# main.net
KiCad netlist of a schematic drawn in Altium Designer
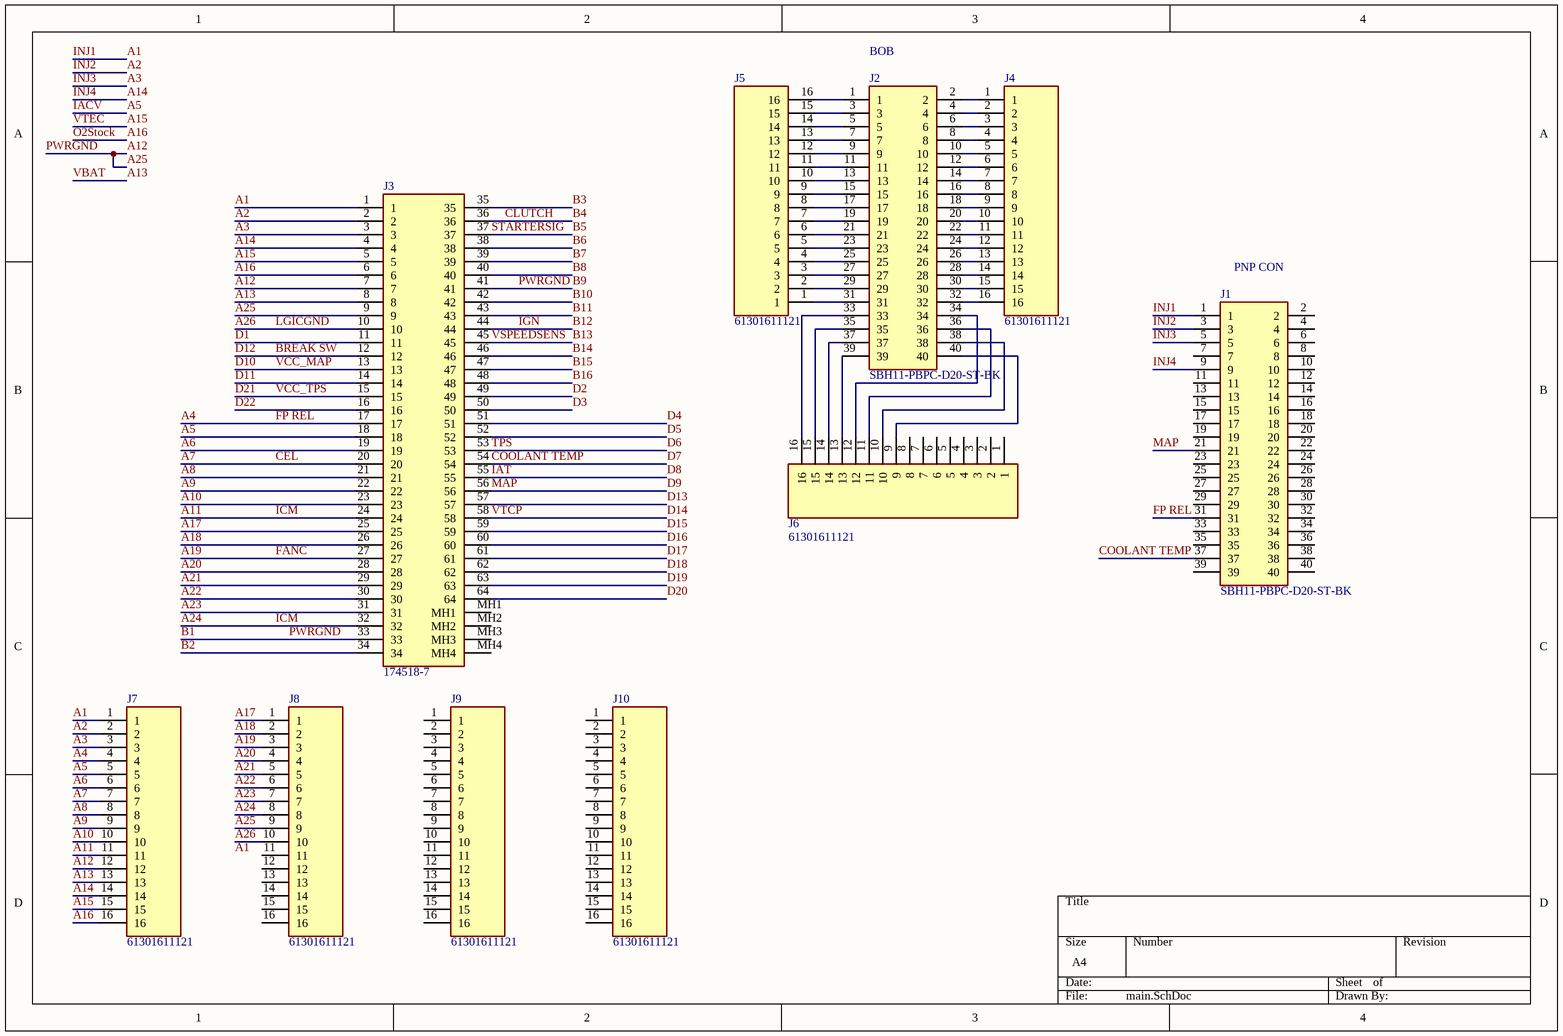
[diagram p0: main.SchDoc]

(export (version "E")
  (design (tool "Eeschema 10.0.6"))
  (components
    (comp (ref "J1")
      (value "SBH11-PBPC-D20-ST-BK")
      (footprint "SamacSys:SHDR40W64P254_2X20_5830X910X910P")
      (description "Connector")
      (libsource (lib "*") (part "SBH11-PBPC-D20-ST-BK"))
    )
    (comp (ref "J2")
      (value "SBH11-PBPC-D20-ST-BK")
      (footprint "SamacSys:SHDR40W64P254_2X20_5830X910X910P")
      (description "Connector")
      (libsource (lib "*") (part "SBH11-PBPC-D20-ST-BK"))
    )
    (comp (ref "J3")
      (value "174518-7")
      (footprint "SamacSys:1745187")
      (description "Connector")
      (fields (field (name "MOUSER PART NUMBER") "571-174518-7"))
      (libsource (lib "*") (part "174518-7"))
    )
    (comp (ref "J4")
      (value "61301611121")
      (footprint "SamacSys:HDRV16W79P0X254_1X16_4064X254X874P")
      (description "Connector")
      (fields (field (name "MOUSER PART NUMBER") "710-61301611121"))
      (libsource (lib "*") (part "61301611121"))
    )
    (comp (ref "J5")
      (value "61301611121")
      (footprint "SamacSys:HDRV16W79P0X254_1X16_4064X254X874P")
      (description "Connector")
      (fields (field (name "MOUSER PART NUMBER") "710-61301611121"))
      (libsource (lib "") (part "61301611121_2"))
    )
    (comp (ref "J6")
      (value "61301611121")
      (footprint "SamacSys:HDRV16W79P0X254_1X16_4064X254X874P")
      (description "Connector")
      (fields (field (name "MOUSER PART NUMBER") "710-61301611121"))
      (libsource (lib "") (part "61301611121_1"))
    )
    (comp (ref "J7")
      (value "61301611121")
      (footprint "SamacSys:HDRV16W79P0X254_1X16_4064X254X874P")
      (description "Connector")
      (fields (field (name "MOUSER PART NUMBER") "710-61301611121"))
      (libsource (lib "*") (part "61301611121"))
    )
    (comp (ref "J8")
      (value "61301611121")
      (footprint "SamacSys:HDRV16W79P0X254_1X16_4064X254X874P")
      (description "Connector")
      (fields (field (name "MOUSER PART NUMBER") "710-61301611121"))
      (libsource (lib "*") (part "61301611121"))
    )
    (comp (ref "J9")
      (value "61301611121")
      (footprint "SamacSys:HDRV16W79P0X254_1X16_4064X254X874P")
      (description "Connector")
      (fields (field (name "MOUSER PART NUMBER") "710-61301611121"))
      (libsource (lib "*") (part "61301611121"))
    )
    (comp (ref "J10")
      (value "61301611121")
      (footprint "SamacSys:HDRV16W79P0X254_1X16_4064X254X874P")
      (description "Connector")
      (fields (field (name "MOUSER PART NUMBER") "710-61301611121"))
      (libsource (lib "*") (part "61301611121"))
    )
  )
  (nets
    (net (code "1") (name "/A1") (class "Default")
      (node (ref "J1") (pin "1") (pinfunction "1_1") (pintype "passive"))
      (node (ref "J3") (pin "1") (pinfunction "1_1") (pintype "passive"))
      (node (ref "J7") (pin "1") (pinfunction "1_1") (pintype "passive"))
    )
    (net (code "2") (name "/A2") (class "Default")
      (node (ref "J1") (pin "3") (pinfunction "3_3") (pintype "passive"))
      (node (ref "J3") (pin "2") (pinfunction "2_2") (pintype "passive"))
      (node (ref "J7") (pin "2") (pinfunction "2_2") (pintype "passive"))
    )
    (net (code "3") (name "/A3") (class "Default")
      (node (ref "J1") (pin "5") (pinfunction "5_5") (pintype "passive"))
      (node (ref "J3") (pin "3") (pinfunction "3_3") (pintype "passive"))
      (node (ref "J7") (pin "3") (pinfunction "3_3") (pintype "passive"))
    )
    (net (code "4") (name "/A4") (class "Default")
      (node (ref "J1") (pin "31") (pinfunction "31_31") (pintype "passive"))
      (node (ref "J3") (pin "17") (pinfunction "17_17") (pintype "passive"))
      (node (ref "J7") (pin "4") (pinfunction "4_4") (pintype "passive"))
    )
    (net (code "5") (name "/A5") (class "Default")
      (node (ref "J3") (pin "18") (pinfunction "18_18") (pintype "passive"))
      (node (ref "J7") (pin "5") (pinfunction "5_5") (pintype "passive"))
    )
    (net (code "6") (name "/A6") (class "Default")
      (node (ref "J3") (pin "19") (pinfunction "19_19") (pintype "passive"))
      (node (ref "J7") (pin "6") (pinfunction "6_6") (pintype "passive"))
    )
    (net (code "7") (name "/A7") (class "Default")
      (node (ref "J3") (pin "20") (pinfunction "20_20") (pintype "passive"))
      (node (ref "J7") (pin "7") (pinfunction "7_7") (pintype "passive"))
    )
    (net (code "8") (name "/A8") (class "Default")
      (node (ref "J3") (pin "21") (pinfunction "21_21") (pintype "passive"))
      (node (ref "J7") (pin "8") (pinfunction "8_8") (pintype "passive"))
    )
    (net (code "9") (name "/A9") (class "Default")
      (node (ref "J3") (pin "22") (pinfunction "22_22") (pintype "passive"))
      (node (ref "J7") (pin "9") (pinfunction "9_9") (pintype "passive"))
    )
    (net (code "10") (name "/A10") (class "Default")
      (node (ref "J3") (pin "23") (pinfunction "23_23") (pintype "passive"))
      (node (ref "J7") (pin "10") (pinfunction "10_10") (pintype "passive"))
    )
    (net (code "11") (name "/A11") (class "Default")
      (node (ref "J3") (pin "24") (pinfunction "24_24") (pintype "passive"))
      (node (ref "J3") (pin "32") (pinfunction "32_32") (pintype "passive"))
      (node (ref "J7") (pin "11") (pinfunction "11_11") (pintype "passive"))
      (node (ref "J8") (pin "8") (pinfunction "8_8") (pintype "passive"))
    )
    (net (code "12") (name "/A12") (class "Default")
      (node (ref "J3") (pin "33") (pinfunction "33_33") (pintype "passive"))
      (node (ref "J3") (pin "41") (pinfunction "41_41") (pintype "passive"))
      (node (ref "J3") (pin "7") (pinfunction "7_7") (pintype "passive"))
      (node (ref "J3") (pin "9") (pinfunction "9_9") (pintype "passive"))
      (node (ref "J7") (pin "12") (pinfunction "12_12") (pintype "passive"))
      (node (ref "J8") (pin "9") (pinfunction "9_9") (pintype "passive"))
    )
    (net (code "13") (name "/A13") (class "Default")
      (node (ref "J3") (pin "8") (pinfunction "8_8") (pintype "passive"))
      (node (ref "J7") (pin "13") (pinfunction "13_13") (pintype "passive"))
    )
    (net (code "14") (name "/A14") (class "Default")
      (node (ref "J1") (pin "9") (pinfunction "9_9") (pintype "passive"))
      (node (ref "J3") (pin "4") (pinfunction "4_4") (pintype "passive"))
      (node (ref "J7") (pin "14") (pinfunction "14_14") (pintype "passive"))
    )
    (net (code "15") (name "/A15") (class "Default")
      (node (ref "J3") (pin "5") (pinfunction "5_5") (pintype "passive"))
      (node (ref "J7") (pin "15") (pinfunction "15_15") (pintype "passive"))
    )
    (net (code "16") (name "/A16") (class "Default")
      (node (ref "J3") (pin "6") (pinfunction "6_6") (pintype "passive"))
      (node (ref "J7") (pin "16") (pinfunction "16_16") (pintype "passive"))
    )
    (net (code "17") (name "/A17") (class "Default")
      (node (ref "J3") (pin "25") (pinfunction "25_25") (pintype "passive"))
      (node (ref "J8") (pin "1") (pinfunction "1_1") (pintype "passive"))
    )
    (net (code "18") (name "/A18") (class "Default")
      (node (ref "J3") (pin "26") (pinfunction "26_26") (pintype "passive"))
      (node (ref "J8") (pin "2") (pinfunction "2_2") (pintype "passive"))
    )
    (net (code "19") (name "/A19") (class "Default")
      (node (ref "J3") (pin "27") (pinfunction "27_27") (pintype "passive"))
      (node (ref "J8") (pin "3") (pinfunction "3_3") (pintype "passive"))
    )
    (net (code "20") (name "/A20") (class "Default")
      (node (ref "J3") (pin "28") (pinfunction "28_28") (pintype "passive"))
      (node (ref "J8") (pin "4") (pinfunction "4_4") (pintype "passive"))
    )
    (net (code "21") (name "/A21") (class "Default")
      (node (ref "J3") (pin "29") (pinfunction "29_29") (pintype "passive"))
      (node (ref "J8") (pin "5") (pinfunction "5_5") (pintype "passive"))
    )
    (net (code "22") (name "/A22") (class "Default")
      (node (ref "J3") (pin "30") (pinfunction "30_30") (pintype "passive"))
      (node (ref "J8") (pin "6") (pinfunction "6_6") (pintype "passive"))
    )
    (net (code "23") (name "/A23") (class "Default")
      (node (ref "J3") (pin "31") (pinfunction "31_31") (pintype "passive"))
      (node (ref "J8") (pin "7") (pinfunction "7_7") (pintype "passive"))
    )
    (net (code "24") (name "/A26") (class "Default")
      (node (ref "J3") (pin "10") (pinfunction "10_10") (pintype "passive"))
      (node (ref "J8") (pin "10") (pinfunction "10_10") (pintype "passive"))
    )
    (net (code "25") (name "/B2") (class "Default")
      (node (ref "J3") (pin "34") (pinfunction "34_34") (pintype "passive"))
    )
    (net (code "26") (name "/B3") (class "Default")
      (node (ref "J3") (pin "35") (pinfunction "35_35") (pintype "passive"))
    )
    (net (code "27") (name "/B4") (class "Default")
      (node (ref "J3") (pin "36") (pinfunction "36_36") (pintype "passive"))
    )
    (net (code "28") (name "/B5") (class "Default")
      (node (ref "J3") (pin "37") (pinfunction "37_37") (pintype "passive"))
    )
    (net (code "29") (name "/B6") (class "Default")
      (node (ref "J3") (pin "38") (pinfunction "38_38") (pintype "passive"))
    )
    (net (code "30") (name "/B7") (class "Default")
      (node (ref "J3") (pin "39") (pinfunction "39_39") (pintype "passive"))
    )
    (net (code "31") (name "/B8") (class "Default")
      (node (ref "J3") (pin "40") (pinfunction "40_40") (pintype "passive"))
    )
    (net (code "32") (name "/B10") (class "Default")
      (node (ref "J3") (pin "42") (pinfunction "42_42") (pintype "passive"))
    )
    (net (code "33") (name "/B11") (class "Default")
      (node (ref "J3") (pin "43") (pinfunction "43_43") (pintype "passive"))
    )
    (net (code "34") (name "/B12") (class "Default")
      (node (ref "J3") (pin "44") (pinfunction "44_44") (pintype "passive"))
    )
    (net (code "35") (name "/B13") (class "Default")
      (node (ref "J3") (pin "45") (pinfunction "45_45") (pintype "passive"))
    )
    (net (code "36") (name "/B14") (class "Default")
      (node (ref "J3") (pin "46") (pinfunction "46_46") (pintype "passive"))
    )
    (net (code "37") (name "/B15") (class "Default")
      (node (ref "J3") (pin "47") (pinfunction "47_47") (pintype "passive"))
    )
    (net (code "38") (name "/B16") (class "Default")
      (node (ref "J3") (pin "48") (pinfunction "48_48") (pintype "passive"))
    )
    (net (code "39") (name "/BREAK SW") (class "Default")
      (node (ref "J3") (pin "12") (pinfunction "12_12") (pintype "passive"))
    )
    (net (code "40") (name "/COOLANT TEMP") (class "Default")
      (node (ref "J1") (pin "37") (pinfunction "37_37") (pintype "passive"))
      (node (ref "J3") (pin "54") (pinfunction "54_54") (pintype "passive"))
    )
    (net (code "41") (name "/D1") (class "Default")
      (node (ref "J3") (pin "11") (pinfunction "11_11") (pintype "passive"))
    )
    (net (code "42") (name "/D2") (class "Default")
      (node (ref "J3") (pin "49") (pinfunction "49_49") (pintype "passive"))
    )
    (net (code "43") (name "/D3") (class "Default")
      (node (ref "J3") (pin "50") (pinfunction "50_50") (pintype "passive"))
    )
    (net (code "44") (name "/D4") (class "Default")
      (node (ref "J3") (pin "51") (pinfunction "51_51") (pintype "passive"))
    )
    (net (code "45") (name "/D5") (class "Default")
      (node (ref "J3") (pin "52") (pinfunction "52_52") (pintype "passive"))
    )
    (net (code "46") (name "/D6") (class "Default")
      (node (ref "J3") (pin "53") (pinfunction "53_53") (pintype "passive"))
    )
    (net (code "47") (name "/D8") (class "Default")
      (node (ref "J3") (pin "55") (pinfunction "55_55") (pintype "passive"))
    )
    (net (code "48") (name "/D9") (class "Default")
      (node (ref "J1") (pin "21") (pinfunction "21_21") (pintype "passive"))
      (node (ref "J3") (pin "56") (pinfunction "56_56") (pintype "passive"))
    )
    (net (code "49") (name "/D10") (class "Default")
      (node (ref "J3") (pin "13") (pinfunction "13_13") (pintype "passive"))
    )
    (net (code "50") (name "/D11") (class "Default")
      (node (ref "J3") (pin "14") (pinfunction "14_14") (pintype "passive"))
    )
    (net (code "51") (name "/D13") (class "Default")
      (node (ref "J3") (pin "57") (pinfunction "57_57") (pintype "passive"))
    )
    (net (code "52") (name "/D14") (class "Default")
      (node (ref "J3") (pin "58") (pinfunction "58_58") (pintype "passive"))
    )
    (net (code "53") (name "/D15") (class "Default")
      (node (ref "J3") (pin "59") (pinfunction "59_59") (pintype "passive"))
    )
    (net (code "54") (name "/D16") (class "Default")
      (node (ref "J3") (pin "60") (pinfunction "60_60") (pintype "passive"))
    )
    (net (code "55") (name "/D17") (class "Default")
      (node (ref "J3") (pin "61") (pinfunction "61_61") (pintype "passive"))
    )
    (net (code "56") (name "/D18") (class "Default")
      (node (ref "J3") (pin "62") (pinfunction "62_62") (pintype "passive"))
    )
    (net (code "57") (name "/D19") (class "Default")
      (node (ref "J3") (pin "63") (pinfunction "63_63") (pintype "passive"))
    )
    (net (code "58") (name "/D20") (class "Default")
      (node (ref "J3") (pin "64") (pinfunction "64_64") (pintype "passive"))
    )
    (net (code "59") (name "/D21") (class "Default")
      (node (ref "J3") (pin "15") (pinfunction "15_15") (pintype "passive"))
    )
    (net (code "60") (name "/D22") (class "Default")
      (node (ref "J3") (pin "16") (pinfunction "16_16") (pintype "passive"))
    )
    (net (code "61") (name "Net-(J2-Pad1)") (class "Default")
      (node (ref "J2") (pin "1") (pinfunction "1_1") (pintype "passive"))
      (node (ref "J5") (pin "16") (pinfunction "16_16") (pintype "passive"))
    )
    (net (code "62") (name "Net-(J2-Pad2)") (class "Default")
      (node (ref "J2") (pin "2") (pinfunction "2_2") (pintype "passive"))
      (node (ref "J4") (pin "1") (pinfunction "1_1") (pintype "passive"))
    )
    (net (code "63") (name "Net-(J2-Pad3)") (class "Default")
      (node (ref "J2") (pin "3") (pinfunction "3_3") (pintype "passive"))
      (node (ref "J5") (pin "15") (pinfunction "15_15") (pintype "passive"))
    )
    (net (code "64") (name "Net-(J2-Pad4)") (class "Default")
      (node (ref "J2") (pin "4") (pinfunction "4_4") (pintype "passive"))
      (node (ref "J4") (pin "2") (pinfunction "2_2") (pintype "passive"))
    )
    (net (code "65") (name "Net-(J2-Pad5)") (class "Default")
      (node (ref "J2") (pin "5") (pinfunction "5_5") (pintype "passive"))
      (node (ref "J5") (pin "14") (pinfunction "14_14") (pintype "passive"))
    )
    (net (code "66") (name "Net-(J2-Pad6)") (class "Default")
      (node (ref "J2") (pin "6") (pinfunction "6_6") (pintype "passive"))
      (node (ref "J4") (pin "3") (pinfunction "3_3") (pintype "passive"))
    )
    (net (code "67") (name "Net-(J2-Pad7)") (class "Default")
      (node (ref "J2") (pin "7") (pinfunction "7_7") (pintype "passive"))
      (node (ref "J5") (pin "13") (pinfunction "13_13") (pintype "passive"))
    )
    (net (code "68") (name "Net-(J2-Pad8)") (class "Default")
      (node (ref "J2") (pin "8") (pinfunction "8_8") (pintype "passive"))
      (node (ref "J4") (pin "4") (pinfunction "4_4") (pintype "passive"))
    )
    (net (code "69") (name "Net-(J2-Pad9)") (class "Default")
      (node (ref "J2") (pin "9") (pinfunction "9_9") (pintype "passive"))
      (node (ref "J5") (pin "12") (pinfunction "12_12") (pintype "passive"))
    )
    (net (code "70") (name "Net-(J2-Pad10)") (class "Default")
      (node (ref "J2") (pin "10") (pinfunction "10_10") (pintype "passive"))
      (node (ref "J4") (pin "5") (pinfunction "5_5") (pintype "passive"))
    )
    (net (code "71") (name "Net-(J2-Pad11)") (class "Default")
      (node (ref "J2") (pin "11") (pinfunction "11_11") (pintype "passive"))
      (node (ref "J5") (pin "11") (pinfunction "11_11") (pintype "passive"))
    )
    (net (code "72") (name "Net-(J2-Pad12)") (class "Default")
      (node (ref "J2") (pin "12") (pinfunction "12_12") (pintype "passive"))
      (node (ref "J4") (pin "6") (pinfunction "6_6") (pintype "passive"))
    )
    (net (code "73") (name "Net-(J2-Pad13)") (class "Default")
      (node (ref "J2") (pin "13") (pinfunction "13_13") (pintype "passive"))
      (node (ref "J5") (pin "10") (pinfunction "10_10") (pintype "passive"))
    )
    (net (code "74") (name "Net-(J2-Pad14)") (class "Default")
      (node (ref "J2") (pin "14") (pinfunction "14_14") (pintype "passive"))
      (node (ref "J4") (pin "7") (pinfunction "7_7") (pintype "passive"))
    )
    (net (code "75") (name "Net-(J2-Pad15)") (class "Default")
      (node (ref "J2") (pin "15") (pinfunction "15_15") (pintype "passive"))
      (node (ref "J5") (pin "9") (pinfunction "9_9") (pintype "passive"))
    )
    (net (code "76") (name "Net-(J2-Pad16)") (class "Default")
      (node (ref "J2") (pin "16") (pinfunction "16_16") (pintype "passive"))
      (node (ref "J4") (pin "8") (pinfunction "8_8") (pintype "passive"))
    )
    (net (code "77") (name "Net-(J2-Pad17)") (class "Default")
      (node (ref "J2") (pin "17") (pinfunction "17_17") (pintype "passive"))
      (node (ref "J5") (pin "8") (pinfunction "8_8") (pintype "passive"))
    )
    (net (code "78") (name "Net-(J2-Pad18)") (class "Default")
      (node (ref "J2") (pin "18") (pinfunction "18_18") (pintype "passive"))
      (node (ref "J4") (pin "9") (pinfunction "9_9") (pintype "passive"))
    )
    (net (code "79") (name "Net-(J2-Pad19)") (class "Default")
      (node (ref "J2") (pin "19") (pinfunction "19_19") (pintype "passive"))
      (node (ref "J5") (pin "7") (pinfunction "7_7") (pintype "passive"))
    )
    (net (code "80") (name "Net-(J2-Pad20)") (class "Default")
      (node (ref "J2") (pin "20") (pinfunction "20_20") (pintype "passive"))
      (node (ref "J4") (pin "10") (pinfunction "10_10") (pintype "passive"))
    )
    (net (code "81") (name "Net-(J2-Pad21)") (class "Default")
      (node (ref "J2") (pin "21") (pinfunction "21_21") (pintype "passive"))
      (node (ref "J5") (pin "6") (pinfunction "6_6") (pintype "passive"))
    )
    (net (code "82") (name "Net-(J2-Pad22)") (class "Default")
      (node (ref "J2") (pin "22") (pinfunction "22_22") (pintype "passive"))
      (node (ref "J4") (pin "11") (pinfunction "11_11") (pintype "passive"))
    )
    (net (code "83") (name "Net-(J2-Pad23)") (class "Default")
      (node (ref "J2") (pin "23") (pinfunction "23_23") (pintype "passive"))
      (node (ref "J5") (pin "5") (pinfunction "5_5") (pintype "passive"))
    )
    (net (code "84") (name "Net-(J2-Pad24)") (class "Default")
      (node (ref "J2") (pin "24") (pinfunction "24_24") (pintype "passive"))
      (node (ref "J4") (pin "12") (pinfunction "12_12") (pintype "passive"))
    )
    (net (code "85") (name "Net-(J2-Pad25)") (class "Default")
      (node (ref "J2") (pin "25") (pinfunction "25_25") (pintype "passive"))
      (node (ref "J5") (pin "4") (pinfunction "4_4") (pintype "passive"))
    )
    (net (code "86") (name "Net-(J2-Pad26)") (class "Default")
      (node (ref "J2") (pin "26") (pinfunction "26_26") (pintype "passive"))
      (node (ref "J4") (pin "13") (pinfunction "13_13") (pintype "passive"))
    )
    (net (code "87") (name "Net-(J2-Pad27)") (class "Default")
      (node (ref "J2") (pin "27") (pinfunction "27_27") (pintype "passive"))
      (node (ref "J5") (pin "3") (pinfunction "3_3") (pintype "passive"))
    )
    (net (code "88") (name "Net-(J2-Pad28)") (class "Default")
      (node (ref "J2") (pin "28") (pinfunction "28_28") (pintype "passive"))
      (node (ref "J4") (pin "14") (pinfunction "14_14") (pintype "passive"))
    )
    (net (code "89") (name "Net-(J2-Pad29)") (class "Default")
      (node (ref "J2") (pin "29") (pinfunction "29_29") (pintype "passive"))
      (node (ref "J5") (pin "2") (pinfunction "2_2") (pintype "passive"))
    )
    (net (code "90") (name "Net-(J2-Pad30)") (class "Default")
      (node (ref "J2") (pin "30") (pinfunction "30_30") (pintype "passive"))
      (node (ref "J4") (pin "15") (pinfunction "15_15") (pintype "passive"))
    )
    (net (code "91") (name "Net-(J2-Pad31)") (class "Default")
      (node (ref "J2") (pin "31") (pinfunction "31_31") (pintype "passive"))
      (node (ref "J5") (pin "1") (pinfunction "1_1") (pintype "passive"))
    )
    (net (code "92") (name "Net-(J2-Pad32)") (class "Default")
      (node (ref "J2") (pin "32") (pinfunction "32_32") (pintype "passive"))
      (node (ref "J4") (pin "16") (pinfunction "16_16") (pintype "passive"))
    )
    (net (code "93") (name "Net-(J2-Pad33)") (class "Default")
      (node (ref "J2") (pin "33") (pinfunction "33_33") (pintype "passive"))
      (node (ref "J6") (pin "16") (pinfunction "16_16") (pintype "passive"))
    )
    (net (code "94") (name "Net-(J2-Pad34)") (class "Default")
      (node (ref "J2") (pin "34") (pinfunction "34_34") (pintype "passive"))
      (node (ref "J6") (pin "12") (pinfunction "12_12") (pintype "passive"))
    )
    (net (code "95") (name "Net-(J2-Pad35)") (class "Default")
      (node (ref "J2") (pin "35") (pinfunction "35_35") (pintype "passive"))
      (node (ref "J6") (pin "15") (pinfunction "15_15") (pintype "passive"))
    )
    (net (code "96") (name "Net-(J2-Pad36)") (class "Default")
      (node (ref "J2") (pin "36") (pinfunction "36_36") (pintype "passive"))
      (node (ref "J6") (pin "11") (pinfunction "11_11") (pintype "passive"))
    )
    (net (code "97") (name "Net-(J2-Pad37)") (class "Default")
      (node (ref "J2") (pin "37") (pinfunction "37_37") (pintype "passive"))
      (node (ref "J6") (pin "14") (pinfunction "14_14") (pintype "passive"))
    )
    (net (code "98") (name "Net-(J2-Pad38)") (class "Default")
      (node (ref "J2") (pin "38") (pinfunction "38_38") (pintype "passive"))
      (node (ref "J6") (pin "10") (pinfunction "10_10") (pintype "passive"))
    )
    (net (code "99") (name "Net-(J2-Pad39)") (class "Default")
      (node (ref "J2") (pin "39") (pinfunction "39_39") (pintype "passive"))
      (node (ref "J6") (pin "13") (pinfunction "13_13") (pintype "passive"))
    )
    (net (code "100") (name "Net-(J2-Pad40)") (class "Default")
      (node (ref "J2") (pin "40") (pinfunction "40_40") (pintype "passive"))
      (node (ref "J6") (pin "9") (pinfunction "9_9") (pintype "passive"))
    )
    (net (code "101") (name "unconnected-(J1-Pad2)") (class "Default")
      (node (ref "J1") (pin "2") (pinfunction "2_2") (pintype "passive"))
    )
    (net (code "102") (name "unconnected-(J1-Pad4)") (class "Default")
      (node (ref "J1") (pin "4") (pinfunction "4_4") (pintype "passive"))
    )
    (net (code "103") (name "unconnected-(J1-Pad6)") (class "Default")
      (node (ref "J1") (pin "6") (pinfunction "6_6") (pintype "passive"))
    )
    (net (code "104") (name "unconnected-(J1-Pad7)") (class "Default")
      (node (ref "J1") (pin "7") (pinfunction "7_7") (pintype "passive"))
    )
    (net (code "105") (name "unconnected-(J1-Pad8)") (class "Default")
      (node (ref "J1") (pin "8") (pinfunction "8_8") (pintype "passive"))
    )
    (net (code "106") (name "unconnected-(J1-Pad10)") (class "Default")
      (node (ref "J1") (pin "10") (pinfunction "10_10") (pintype "passive"))
    )
    (net (code "107") (name "unconnected-(J1-Pad11)") (class "Default")
      (node (ref "J1") (pin "11") (pinfunction "11_11") (pintype "passive"))
    )
    (net (code "108") (name "unconnected-(J1-Pad12)") (class "Default")
      (node (ref "J1") (pin "12") (pinfunction "12_12") (pintype "passive"))
    )
    (net (code "109") (name "unconnected-(J1-Pad13)") (class "Default")
      (node (ref "J1") (pin "13") (pinfunction "13_13") (pintype "passive"))
    )
    (net (code "110") (name "unconnected-(J1-Pad14)") (class "Default")
      (node (ref "J1") (pin "14") (pinfunction "14_14") (pintype "passive"))
    )
    (net (code "111") (name "unconnected-(J1-Pad15)") (class "Default")
      (node (ref "J1") (pin "15") (pinfunction "15_15") (pintype "passive"))
    )
    (net (code "112") (name "unconnected-(J1-Pad16)") (class "Default")
      (node (ref "J1") (pin "16") (pinfunction "16_16") (pintype "passive"))
    )
    (net (code "113") (name "unconnected-(J1-Pad17)") (class "Default")
      (node (ref "J1") (pin "17") (pinfunction "17_17") (pintype "passive"))
    )
    (net (code "114") (name "unconnected-(J1-Pad18)") (class "Default")
      (node (ref "J1") (pin "18") (pinfunction "18_18") (pintype "passive"))
    )
    (net (code "115") (name "unconnected-(J1-Pad19)") (class "Default")
      (node (ref "J1") (pin "19") (pinfunction "19_19") (pintype "passive"))
    )
    (net (code "116") (name "unconnected-(J1-Pad20)") (class "Default")
      (node (ref "J1") (pin "20") (pinfunction "20_20") (pintype "passive"))
    )
    (net (code "117") (name "unconnected-(J1-Pad22)") (class "Default")
      (node (ref "J1") (pin "22") (pinfunction "22_22") (pintype "passive"))
    )
    (net (code "118") (name "unconnected-(J1-Pad23)") (class "Default")
      (node (ref "J1") (pin "23") (pinfunction "23_23") (pintype "passive"))
    )
    (net (code "119") (name "unconnected-(J1-Pad24)") (class "Default")
      (node (ref "J1") (pin "24") (pinfunction "24_24") (pintype "passive"))
    )
    (net (code "120") (name "unconnected-(J1-Pad25)") (class "Default")
      (node (ref "J1") (pin "25") (pinfunction "25_25") (pintype "passive"))
    )
    (net (code "121") (name "unconnected-(J1-Pad26)") (class "Default")
      (node (ref "J1") (pin "26") (pinfunction "26_26") (pintype "passive"))
    )
    (net (code "122") (name "unconnected-(J1-Pad27)") (class "Default")
      (node (ref "J1") (pin "27") (pinfunction "27_27") (pintype "passive"))
    )
    (net (code "123") (name "unconnected-(J1-Pad28)") (class "Default")
      (node (ref "J1") (pin "28") (pinfunction "28_28") (pintype "passive"))
    )
    (net (code "124") (name "unconnected-(J1-Pad29)") (class "Default")
      (node (ref "J1") (pin "29") (pinfunction "29_29") (pintype "passive"))
    )
    (net (code "125") (name "unconnected-(J1-Pad30)") (class "Default")
      (node (ref "J1") (pin "30") (pinfunction "30_30") (pintype "passive"))
    )
    (net (code "126") (name "unconnected-(J1-Pad32)") (class "Default")
      (node (ref "J1") (pin "32") (pinfunction "32_32") (pintype "passive"))
    )
    (net (code "127") (name "unconnected-(J1-Pad33)") (class "Default")
      (node (ref "J1") (pin "33") (pinfunction "33_33") (pintype "passive"))
    )
    (net (code "128") (name "unconnected-(J1-Pad34)") (class "Default")
      (node (ref "J1") (pin "34") (pinfunction "34_34") (pintype "passive"))
    )
    (net (code "129") (name "unconnected-(J1-Pad35)") (class "Default")
      (node (ref "J1") (pin "35") (pinfunction "35_35") (pintype "passive"))
    )
    (net (code "130") (name "unconnected-(J1-Pad36)") (class "Default")
      (node (ref "J1") (pin "36") (pinfunction "36_36") (pintype "passive"))
    )
    (net (code "131") (name "unconnected-(J1-Pad38)") (class "Default")
      (node (ref "J1") (pin "38") (pinfunction "38_38") (pintype "passive"))
    )
    (net (code "132") (name "unconnected-(J1-Pad39)") (class "Default")
      (node (ref "J1") (pin "39") (pinfunction "39_39") (pintype "passive"))
    )
    (net (code "133") (name "unconnected-(J1-Pad40)") (class "Default")
      (node (ref "J1") (pin "40") (pinfunction "40_40") (pintype "passive"))
    )
    (net (code "134") (name "unconnected-(J3-PadMH1)") (class "Default")
      (node (ref "J3") (pin "MH1") (pinfunction "MH1_MH1") (pintype "passive"))
    )
    (net (code "135") (name "unconnected-(J3-PadMH2)") (class "Default")
      (node (ref "J3") (pin "MH2") (pinfunction "MH2_MH2") (pintype "passive"))
    )
    (net (code "136") (name "unconnected-(J3-PadMH3)") (class "Default")
      (node (ref "J3") (pin "MH3") (pinfunction "MH3_MH3") (pintype "passive"))
    )
    (net (code "137") (name "unconnected-(J3-PadMH4)") (class "Default")
      (node (ref "J3") (pin "MH4") (pinfunction "MH4_MH4") (pintype "passive"))
    )
    (net (code "138") (name "unconnected-(J6-Pad1)") (class "Default")
      (node (ref "J6") (pin "1") (pinfunction "1_1") (pintype "passive"))
    )
    (net (code "139") (name "unconnected-(J6-Pad2)") (class "Default")
      (node (ref "J6") (pin "2") (pinfunction "2_2") (pintype "passive"))
    )
    (net (code "140") (name "unconnected-(J6-Pad3)") (class "Default")
      (node (ref "J6") (pin "3") (pinfunction "3_3") (pintype "passive"))
    )
    (net (code "141") (name "unconnected-(J6-Pad4)") (class "Default")
      (node (ref "J6") (pin "4") (pinfunction "4_4") (pintype "passive"))
    )
    (net (code "142") (name "unconnected-(J6-Pad5)") (class "Default")
      (node (ref "J6") (pin "5") (pinfunction "5_5") (pintype "passive"))
    )
    (net (code "143") (name "unconnected-(J6-Pad6)") (class "Default")
      (node (ref "J6") (pin "6") (pinfunction "6_6") (pintype "passive"))
    )
    (net (code "144") (name "unconnected-(J6-Pad7)") (class "Default")
      (node (ref "J6") (pin "7") (pinfunction "7_7") (pintype "passive"))
    )
    (net (code "145") (name "unconnected-(J6-Pad8)") (class "Default")
      (node (ref "J6") (pin "8") (pinfunction "8_8") (pintype "passive"))
    )
    (net (code "146") (name "unconnected-(J8-Pad11)") (class "Default")
      (node (ref "J8") (pin "11") (pinfunction "11_11") (pintype "passive"))
    )
    (net (code "147") (name "unconnected-(J8-Pad12)") (class "Default")
      (node (ref "J8") (pin "12") (pinfunction "12_12") (pintype "passive"))
    )
    (net (code "148") (name "unconnected-(J8-Pad13)") (class "Default")
      (node (ref "J8") (pin "13") (pinfunction "13_13") (pintype "passive"))
    )
    (net (code "149") (name "unconnected-(J8-Pad14)") (class "Default")
      (node (ref "J8") (pin "14") (pinfunction "14_14") (pintype "passive"))
    )
    (net (code "150") (name "unconnected-(J8-Pad15)") (class "Default")
      (node (ref "J8") (pin "15") (pinfunction "15_15") (pintype "passive"))
    )
    (net (code "151") (name "unconnected-(J8-Pad16)") (class "Default")
      (node (ref "J8") (pin "16") (pinfunction "16_16") (pintype "passive"))
    )
    (net (code "152") (name "unconnected-(J9-Pad1)") (class "Default")
      (node (ref "J9") (pin "1") (pinfunction "1_1") (pintype "passive"))
    )
    (net (code "153") (name "unconnected-(J9-Pad2)") (class "Default")
      (node (ref "J9") (pin "2") (pinfunction "2_2") (pintype "passive"))
    )
    (net (code "154") (name "unconnected-(J9-Pad3)") (class "Default")
      (node (ref "J9") (pin "3") (pinfunction "3_3") (pintype "passive"))
    )
    (net (code "155") (name "unconnected-(J9-Pad4)") (class "Default")
      (node (ref "J9") (pin "4") (pinfunction "4_4") (pintype "passive"))
    )
    (net (code "156") (name "unconnected-(J9-Pad5)") (class "Default")
      (node (ref "J9") (pin "5") (pinfunction "5_5") (pintype "passive"))
    )
    (net (code "157") (name "unconnected-(J9-Pad6)") (class "Default")
      (node (ref "J9") (pin "6") (pinfunction "6_6") (pintype "passive"))
    )
    (net (code "158") (name "unconnected-(J9-Pad7)") (class "Default")
      (node (ref "J9") (pin "7") (pinfunction "7_7") (pintype "passive"))
    )
    (net (code "159") (name "unconnected-(J9-Pad8)") (class "Default")
      (node (ref "J9") (pin "8") (pinfunction "8_8") (pintype "passive"))
    )
    (net (code "160") (name "unconnected-(J9-Pad9)") (class "Default")
      (node (ref "J9") (pin "9") (pinfunction "9_9") (pintype "passive"))
    )
    (net (code "161") (name "unconnected-(J9-Pad10)") (class "Default")
      (node (ref "J9") (pin "10") (pinfunction "10_10") (pintype "passive"))
    )
    (net (code "162") (name "unconnected-(J9-Pad11)") (class "Default")
      (node (ref "J9") (pin "11") (pinfunction "11_11") (pintype "passive"))
    )
    (net (code "163") (name "unconnected-(J9-Pad12)") (class "Default")
      (node (ref "J9") (pin "12") (pinfunction "12_12") (pintype "passive"))
    )
    (net (code "164") (name "unconnected-(J9-Pad13)") (class "Default")
      (node (ref "J9") (pin "13") (pinfunction "13_13") (pintype "passive"))
    )
    (net (code "165") (name "unconnected-(J9-Pad14)") (class "Default")
      (node (ref "J9") (pin "14") (pinfunction "14_14") (pintype "passive"))
    )
    (net (code "166") (name "unconnected-(J9-Pad15)") (class "Default")
      (node (ref "J9") (pin "15") (pinfunction "15_15") (pintype "passive"))
    )
    (net (code "167") (name "unconnected-(J9-Pad16)") (class "Default")
      (node (ref "J9") (pin "16") (pinfunction "16_16") (pintype "passive"))
    )
    (net (code "168") (name "unconnected-(J10-Pad1)") (class "Default")
      (node (ref "J10") (pin "1") (pinfunction "1_1") (pintype "passive"))
    )
    (net (code "169") (name "unconnected-(J10-Pad2)") (class "Default")
      (node (ref "J10") (pin "2") (pinfunction "2_2") (pintype "passive"))
    )
    (net (code "170") (name "unconnected-(J10-Pad3)") (class "Default")
      (node (ref "J10") (pin "3") (pinfunction "3_3") (pintype "passive"))
    )
    (net (code "171") (name "unconnected-(J10-Pad4)") (class "Default")
      (node (ref "J10") (pin "4") (pinfunction "4_4") (pintype "passive"))
    )
    (net (code "172") (name "unconnected-(J10-Pad5)") (class "Default")
      (node (ref "J10") (pin "5") (pinfunction "5_5") (pintype "passive"))
    )
    (net (code "173") (name "unconnected-(J10-Pad6)") (class "Default")
      (node (ref "J10") (pin "6") (pinfunction "6_6") (pintype "passive"))
    )
    (net (code "174") (name "unconnected-(J10-Pad7)") (class "Default")
      (node (ref "J10") (pin "7") (pinfunction "7_7") (pintype "passive"))
    )
    (net (code "175") (name "unconnected-(J10-Pad8)") (class "Default")
      (node (ref "J10") (pin "8") (pinfunction "8_8") (pintype "passive"))
    )
    (net (code "176") (name "unconnected-(J10-Pad9)") (class "Default")
      (node (ref "J10") (pin "9") (pinfunction "9_9") (pintype "passive"))
    )
    (net (code "177") (name "unconnected-(J10-Pad10)") (class "Default")
      (node (ref "J10") (pin "10") (pinfunction "10_10") (pintype "passive"))
    )
    (net (code "178") (name "unconnected-(J10-Pad11)") (class "Default")
      (node (ref "J10") (pin "11") (pinfunction "11_11") (pintype "passive"))
    )
    (net (code "179") (name "unconnected-(J10-Pad12)") (class "Default")
      (node (ref "J10") (pin "12") (pinfunction "12_12") (pintype "passive"))
    )
    (net (code "180") (name "unconnected-(J10-Pad13)") (class "Default")
      (node (ref "J10") (pin "13") (pinfunction "13_13") (pintype "passive"))
    )
    (net (code "181") (name "unconnected-(J10-Pad14)") (class "Default")
      (node (ref "J10") (pin "14") (pinfunction "14_14") (pintype "passive"))
    )
    (net (code "182") (name "unconnected-(J10-Pad15)") (class "Default")
      (node (ref "J10") (pin "15") (pinfunction "15_15") (pintype "passive"))
    )
    (net (code "183") (name "unconnected-(J10-Pad16)") (class "Default")
      (node (ref "J10") (pin "16") (pinfunction "16_16") (pintype "passive"))
    )
  )
)
